# Staravia.net
KiCad netlist of a schematic drawn in Altium Designer
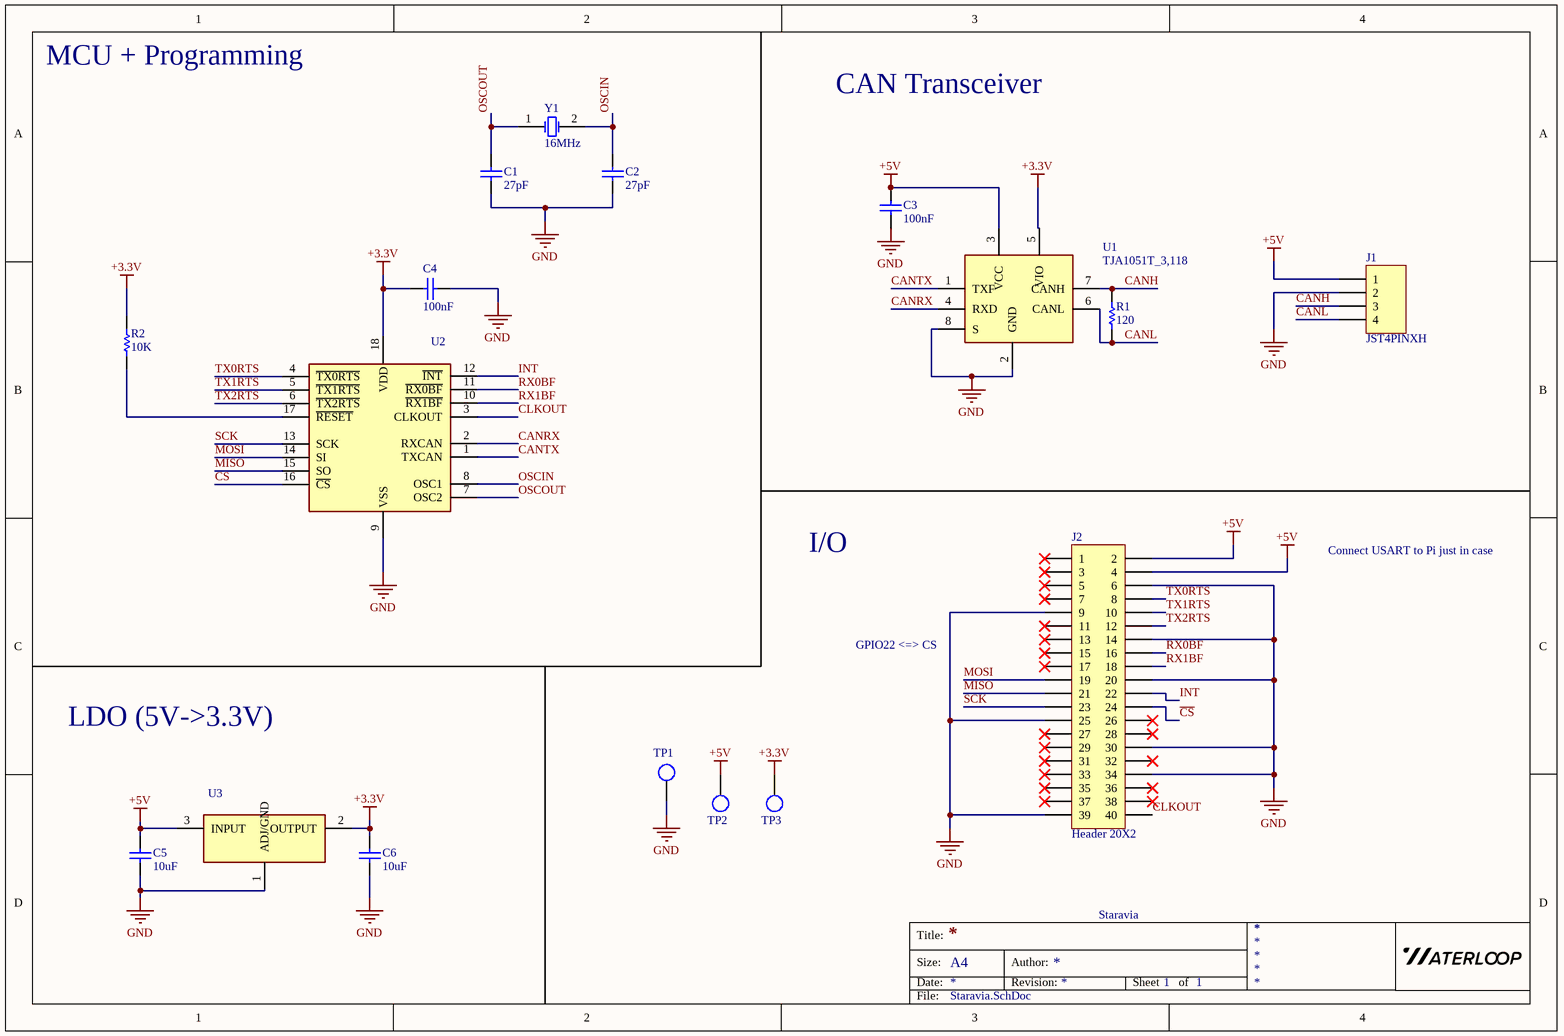
[diagram p0: Staravia.SchDoc]

(export (version "E")
  (design (tool "Eeschema 10.0.6"))
  (components
    (comp (ref "C1")
      (value "27pF")
      (footprint "0805 - Capacitor")
      (description "Nonpolarized Capacitor")
      (fields
        (field (name "MANUFACTURER") "Yageo")
        (field (name "MANUFACTURER PART NUMBER") "CC0805JRNPO9BN270")
      )
      (libsource (lib "General") (part "Capacitor - Nonpolarized"))
    )
    (comp (ref "C2")
      (value "27pF")
      (footprint "0805 - Capacitor")
      (description "Nonpolarized Capacitor")
      (fields
        (field (name "MANUFACTURER") "Yageo")
        (field (name "MANUFACTURER PART NUMBER") "CC0805JRNPO9BN270")
      )
      (libsource (lib "General") (part "Capacitor - Nonpolarized"))
    )
    (comp (ref "C3")
      (value "100nF")
      (footprint "0805 - Capacitor")
      (description "Nonpolarized Capacitor")
      (fields
        (field (name "MANUFACTURER") "Yageo")
        (field (name "MANUFACTURER PART NUMBER") "CC0805KRX7R8BB104")
      )
      (libsource (lib "General") (part "Capacitor - Nonpolarized"))
    )
    (comp (ref "C4")
      (value "100nF")
      (footprint "0805 - Capacitor")
      (description "Nonpolarized Capacitor")
      (fields
        (field (name "MANUFACTURER") "Yageo")
        (field (name "MANUFACTURER PART NUMBER") "CC0805KRX7R8BB104")
      )
      (libsource (lib "General") (part "Capacitor - Nonpolarized"))
    )
    (comp (ref "C5")
      (value "10uF")
      (footprint "0805 - Capacitor")
      (description "Nonpolarized Capacitor")
      (fields
        (field (name "MANUFACTURER") "Yageo")
        (field (name "MANUFACTURER PART NUMBER") "CC0805KFX7R6BB106")
      )
      (libsource (lib "General") (part "Capacitor - Nonpolarized"))
    )
    (comp (ref "C6")
      (value "10uF")
      (footprint "0805 - Capacitor")
      (description "Nonpolarized Capacitor")
      (fields
        (field (name "MANUFACTURER") "Yageo")
        (field (name "MANUFACTURER PART NUMBER") "CC0805KFX7R6BB106")
      )
      (libsource (lib "General") (part "Capacitor - Nonpolarized"))
    )
    (comp (ref "J1")
      (value "JST4PINXH")
      (footprint "B4B-XH")
      (description "1x4 Pin Header")
      (libsource (lib "GeneralConnectors") (part "1x4 Header"))
    )
    (comp (ref "J2")
      (value "Header 20X2")
      (footprint "HDR2X20")
      (description "Header, 20-Pin, Dual row")
      (fields (field (name "PUBLISHER") "Altium Limited"))
      (libsource (lib "Miscellaneous Connectors") (part "Header 20X2"))
    )
    (comp (ref "R1")
      (value "120")
      (footprint "0603 - Resistor")
      (description "Resistor")
      (fields
        (field (name "MANUFACTURER PART NUMBER") "RC0603FR-07120RL")
        (field (name "MANUFACTURER") "Yageo")
      )
      (libsource (lib "General") (part "Resistor"))
    )
    (comp (ref "R2")
      (value "10K")
      (footprint "0603 - Resistor")
      (description "Resistor")
      (fields
        (field (name "MANUFACTURER PART NUMBER") "RC0603FR-0710KL")
        (field (name "MANUFACTURER") "Yageo")
      )
      (libsource (lib "General") (part "Resistor"))
    )
    (comp (ref "TP1")
      (value "Test Point")
      (footprint "Test Point")
      (libsource (lib "General") (part "Test Point"))
    )
    (comp (ref "TP2")
      (value "Test Point")
      (footprint "Test Point")
      (libsource (lib "General") (part "Test Point"))
    )
    (comp (ref "TP3")
      (value "Test Point")
      (footprint "Test Point")
      (libsource (lib "General") (part "Test Point"))
    )
    (comp (ref "U1")
      (value "TJA1051T_3,118")
      (footprint "TJA1051T/3,118")
      (description "CAN Transceiver IC 4.5V-5.5V 250ns")
      (fields (field (name "MANUFACTURER") "NXP") (field (name "MANUFACTURER PART NUMBER") "TJA1051T/3,118"))
      (libsource (lib "GeneralComponents") (part "TJA1051T_3,118"))
    )
    (comp (ref "U2")
      (value "MCP2515-E/SO")
      (footprint "MCP2515-I/ML")
      (description "SPI->CAN Controller")
      (fields (field (name "MANUFACTURER") "Microchip"))
      (libsource (lib "Embedded") (part "MCP2515-E/SO"))
    )
    (comp (ref "U3")
      (value "TLV1117-33IDCYR")
      (footprint "TLV1117")
      (description "Linear Voltage Regulator IC 3.3V 800MA SOT223-4")
      (fields (field (name "MANUFACTURER") "Texas Instruments"))
      (libsource (lib "GeneralComponents") (part "TLV1117-33IDCYR"))
    )
    (comp (ref "Y1")
      (value "16MHz")
      (footprint "2-SMD NO LEAD CRSYSTAL")
      (description "Crystal Oscillator")
      (fields
        (field (name "MANUFACTURER PART NUMBER") "ABM7-16.000MHZ-4-T")
        (field (name "MANUFACTURER") "Abracon LLC")
      )
      (libsource (lib "General") (part "Oscillator"))
    )
  )
  (nets
    (net (code "1") (name "+3.3V") (class "Default")
      (node (ref "C4") (pin "2") (pinfunction "2_2") (pintype "passive"))
      (node (ref "C6") (pin "2") (pinfunction "2_2") (pintype "passive"))
      (node (ref "R2") (pin "2") (pinfunction "2_2") (pintype "passive"))
      (node (ref "TP3") (pin "1") (pinfunction "0_1") (pintype "passive"))
      (node (ref "U1") (pin "5") (pinfunction "VIO_5") (pintype "passive"))
      (node (ref "U2") (pin "18") (pinfunction "VDD_18") (pintype "passive"))
      (node (ref "U3") (pin "2") (pinfunction "OUTPUT_2") (pintype "passive"))
    )
    (net (code "2") (name "+5V") (class "Default")
      (node (ref "C3") (pin "2") (pinfunction "2_2") (pintype "passive"))
      (node (ref "C5") (pin "1") (pinfunction "1_1") (pintype "passive"))
      (node (ref "J1") (pin "1") (pinfunction "1_1") (pintype "passive"))
      (node (ref "J2") (pin "2") (pinfunction "2_2") (pintype "passive"))
      (node (ref "J2") (pin "4") (pinfunction "4_4") (pintype "passive"))
      (node (ref "TP2") (pin "1") (pinfunction "0_1") (pintype "passive"))
      (node (ref "U1") (pin "3") (pinfunction "VCC_3") (pintype "passive"))
      (node (ref "U3") (pin "3") (pinfunction "INPUT_3") (pintype "passive"))
    )
    (net (code "3") (name "/CANH") (class "Default")
      (node (ref "J1") (pin "3") (pinfunction "3_3") (pintype "passive"))
      (node (ref "R1") (pin "2") (pinfunction "2_2") (pintype "passive"))
      (node (ref "U1") (pin "7") (pinfunction "CANH_7") (pintype "passive"))
    )
    (net (code "4") (name "/CANL") (class "Default")
      (node (ref "J1") (pin "4") (pinfunction "4_4") (pintype "passive"))
      (node (ref "R1") (pin "1") (pinfunction "1_1") (pintype "passive"))
      (node (ref "U1") (pin "6") (pinfunction "CANL_6") (pintype "passive"))
    )
    (net (code "5") (name "/CANRX") (class "Default")
      (node (ref "U1") (pin "4") (pinfunction "RXD_4") (pintype "passive"))
      (node (ref "U2") (pin "2") (pinfunction "RXCAN_2") (pintype "passive"))
    )
    (net (code "6") (name "/CANTX") (class "Default")
      (node (ref "U1") (pin "1") (pinfunction "TXF_1") (pintype "passive"))
      (node (ref "U2") (pin "1") (pinfunction "TXCAN_1") (pintype "passive"))
    )
    (net (code "7") (name "/CLKOUT") (class "Default")
      (node (ref "J2") (pin "40") (pinfunction "40_40") (pintype "passive"))
      (node (ref "U2") (pin "3") (pinfunction "CLKOUT_3") (pintype "passive"))
    )
    (net (code "8") (name "/INT") (class "Default")
      (node (ref "J2") (pin "22") (pinfunction "22_22") (pintype "passive"))
      (node (ref "U2") (pin "12") (pinfunction "~{INT}_12") (pintype "passive"))
    )
    (net (code "9") (name "/MISO") (class "Default")
      (node (ref "J2") (pin "21") (pinfunction "21_21") (pintype "passive"))
      (node (ref "U2") (pin "15") (pinfunction "SO_15") (pintype "passive"))
    )
    (net (code "10") (name "/MOSI") (class "Default")
      (node (ref "J2") (pin "19") (pinfunction "19_19") (pintype "passive"))
      (node (ref "U2") (pin "14") (pinfunction "SI_14") (pintype "passive"))
    )
    (net (code "11") (name "/OSCIN") (class "Default")
      (node (ref "C2") (pin "2") (pinfunction "2_2") (pintype "passive"))
      (node (ref "U2") (pin "8") (pinfunction "OSC1_8") (pintype "passive"))
      (node (ref "Y1") (pin "2") (pinfunction "OSC2_2") (pintype "passive"))
    )
    (net (code "12") (name "/OSCOUT") (class "Default")
      (node (ref "C1") (pin "2") (pinfunction "2_2") (pintype "passive"))
      (node (ref "U2") (pin "7") (pinfunction "OSC2_7") (pintype "passive"))
      (node (ref "Y1") (pin "1") (pinfunction "OSC1_1") (pintype "passive"))
    )
    (net (code "13") (name "/RX0BF") (class "Default")
      (node (ref "J2") (pin "16") (pinfunction "16_16") (pintype "passive"))
      (node (ref "U2") (pin "11") (pinfunction "~{RX0BF}_11") (pintype "passive"))
    )
    (net (code "14") (name "/RX1BF") (class "Default")
      (node (ref "J2") (pin "18") (pinfunction "18_18") (pintype "passive"))
      (node (ref "U2") (pin "10") (pinfunction "~{RX1BF}_10") (pintype "passive"))
    )
    (net (code "15") (name "/SCK") (class "Default")
      (node (ref "J2") (pin "23") (pinfunction "23_23") (pintype "passive"))
      (node (ref "U2") (pin "13") (pinfunction "SCK_13") (pintype "passive"))
    )
    (net (code "16") (name "/TX0RTS") (class "Default")
      (node (ref "J2") (pin "8") (pinfunction "8_8") (pintype "passive"))
      (node (ref "U2") (pin "4") (pinfunction "~{TX0RTS}_4") (pintype "passive"))
    )
    (net (code "17") (name "/TX1RTS") (class "Default")
      (node (ref "J2") (pin "10") (pinfunction "10_10") (pintype "passive"))
      (node (ref "U2") (pin "5") (pinfunction "~{TX1RTS}_5") (pintype "passive"))
    )
    (net (code "18") (name "/TX2RTS") (class "Default")
      (node (ref "J2") (pin "12") (pinfunction "12_12") (pintype "passive"))
      (node (ref "U2") (pin "6") (pinfunction "~{TX2RTS}_6") (pintype "passive"))
    )
    (net (code "19") (name "/~{CS}") (class "Default")
      (node (ref "J2") (pin "24") (pinfunction "24_24") (pintype "passive"))
      (node (ref "U2") (pin "16") (pinfunction "~{CS}_16") (pintype "passive"))
    )
    (net (code "20") (name "GND") (class "Default")
      (node (ref "C1") (pin "1") (pinfunction "1_1") (pintype "passive"))
      (node (ref "C2") (pin "1") (pinfunction "1_1") (pintype "passive"))
      (node (ref "C3") (pin "1") (pinfunction "1_1") (pintype "passive"))
      (node (ref "C4") (pin "1") (pinfunction "1_1") (pintype "passive"))
      (node (ref "C5") (pin "2") (pinfunction "2_2") (pintype "passive"))
      (node (ref "C6") (pin "1") (pinfunction "1_1") (pintype "passive"))
      (node (ref "J1") (pin "2") (pinfunction "2_2") (pintype "passive"))
      (node (ref "J2") (pin "14") (pinfunction "14_14") (pintype "passive"))
      (node (ref "J2") (pin "20") (pinfunction "20_20") (pintype "passive"))
      (node (ref "J2") (pin "25") (pinfunction "25_25") (pintype "passive"))
      (node (ref "J2") (pin "30") (pinfunction "30_30") (pintype "passive"))
      (node (ref "J2") (pin "34") (pinfunction "34_34") (pintype "passive"))
      (node (ref "J2") (pin "39") (pinfunction "39_39") (pintype "passive"))
      (node (ref "J2") (pin "6") (pinfunction "6_6") (pintype "passive"))
      (node (ref "J2") (pin "9") (pinfunction "9_9") (pintype "passive"))
      (node (ref "TP1") (pin "1") (pinfunction "0_1") (pintype "passive"))
      (node (ref "U1") (pin "2") (pinfunction "GND_2") (pintype "passive"))
      (node (ref "U1") (pin "8") (pinfunction "S_8") (pintype "passive"))
      (node (ref "U2") (pin "9") (pinfunction "VSS_9") (pintype "passive"))
      (node (ref "U3") (pin "1") (pinfunction "ADJ/GND_1") (pintype "passive"))
    )
    (net (code "21") (name "Net-(U2-~{RESET})") (class "Default")
      (node (ref "R2") (pin "1") (pinfunction "1_1") (pintype "passive"))
      (node (ref "U2") (pin "17") (pinfunction "~{RESET}_17") (pintype "passive"))
    )
    (net (code "22") (name "unconnected-(J2-Pad1)") (class "Default")
      (node (ref "J2") (pin "1") (pinfunction "1_1") (pintype "passive+no_connect"))
    )
    (net (code "23") (name "unconnected-(J2-Pad3)") (class "Default")
      (node (ref "J2") (pin "3") (pinfunction "3_3") (pintype "passive+no_connect"))
    )
    (net (code "24") (name "unconnected-(J2-Pad5)") (class "Default")
      (node (ref "J2") (pin "5") (pinfunction "5_5") (pintype "passive+no_connect"))
    )
    (net (code "25") (name "unconnected-(J2-Pad7)") (class "Default")
      (node (ref "J2") (pin "7") (pinfunction "7_7") (pintype "passive+no_connect"))
    )
    (net (code "26") (name "unconnected-(J2-Pad11)") (class "Default")
      (node (ref "J2") (pin "11") (pinfunction "11_11") (pintype "passive+no_connect"))
    )
    (net (code "27") (name "unconnected-(J2-Pad13)") (class "Default")
      (node (ref "J2") (pin "13") (pinfunction "13_13") (pintype "passive+no_connect"))
    )
    (net (code "28") (name "unconnected-(J2-Pad15)") (class "Default")
      (node (ref "J2") (pin "15") (pinfunction "15_15") (pintype "passive+no_connect"))
    )
    (net (code "29") (name "unconnected-(J2-Pad17)") (class "Default")
      (node (ref "J2") (pin "17") (pinfunction "17_17") (pintype "passive+no_connect"))
    )
    (net (code "30") (name "unconnected-(J2-Pad26)") (class "Default")
      (node (ref "J2") (pin "26") (pinfunction "26_26") (pintype "passive+no_connect"))
    )
    (net (code "31") (name "unconnected-(J2-Pad27)") (class "Default")
      (node (ref "J2") (pin "27") (pinfunction "27_27") (pintype "passive+no_connect"))
    )
    (net (code "32") (name "unconnected-(J2-Pad28)") (class "Default")
      (node (ref "J2") (pin "28") (pinfunction "28_28") (pintype "passive+no_connect"))
    )
    (net (code "33") (name "unconnected-(J2-Pad29)") (class "Default")
      (node (ref "J2") (pin "29") (pinfunction "29_29") (pintype "passive+no_connect"))
    )
    (net (code "34") (name "unconnected-(J2-Pad31)") (class "Default")
      (node (ref "J2") (pin "31") (pinfunction "31_31") (pintype "passive+no_connect"))
    )
    (net (code "35") (name "unconnected-(J2-Pad32)") (class "Default")
      (node (ref "J2") (pin "32") (pinfunction "32_32") (pintype "passive+no_connect"))
    )
    (net (code "36") (name "unconnected-(J2-Pad33)") (class "Default")
      (node (ref "J2") (pin "33") (pinfunction "33_33") (pintype "passive+no_connect"))
    )
    (net (code "37") (name "unconnected-(J2-Pad35)") (class "Default")
      (node (ref "J2") (pin "35") (pinfunction "35_35") (pintype "passive+no_connect"))
    )
    (net (code "38") (name "unconnected-(J2-Pad36)") (class "Default")
      (node (ref "J2") (pin "36") (pinfunction "36_36") (pintype "passive+no_connect"))
    )
    (net (code "39") (name "unconnected-(J2-Pad37)") (class "Default")
      (node (ref "J2") (pin "37") (pinfunction "37_37") (pintype "passive+no_connect"))
    )
    (net (code "40") (name "unconnected-(J2-Pad38)") (class "Default")
      (node (ref "J2") (pin "38") (pinfunction "38_38") (pintype "passive+no_connect"))
    )
  )
)
